# Deneigus_Sensors.net
KiCad netlist of a schematic drawn in Altium Designer
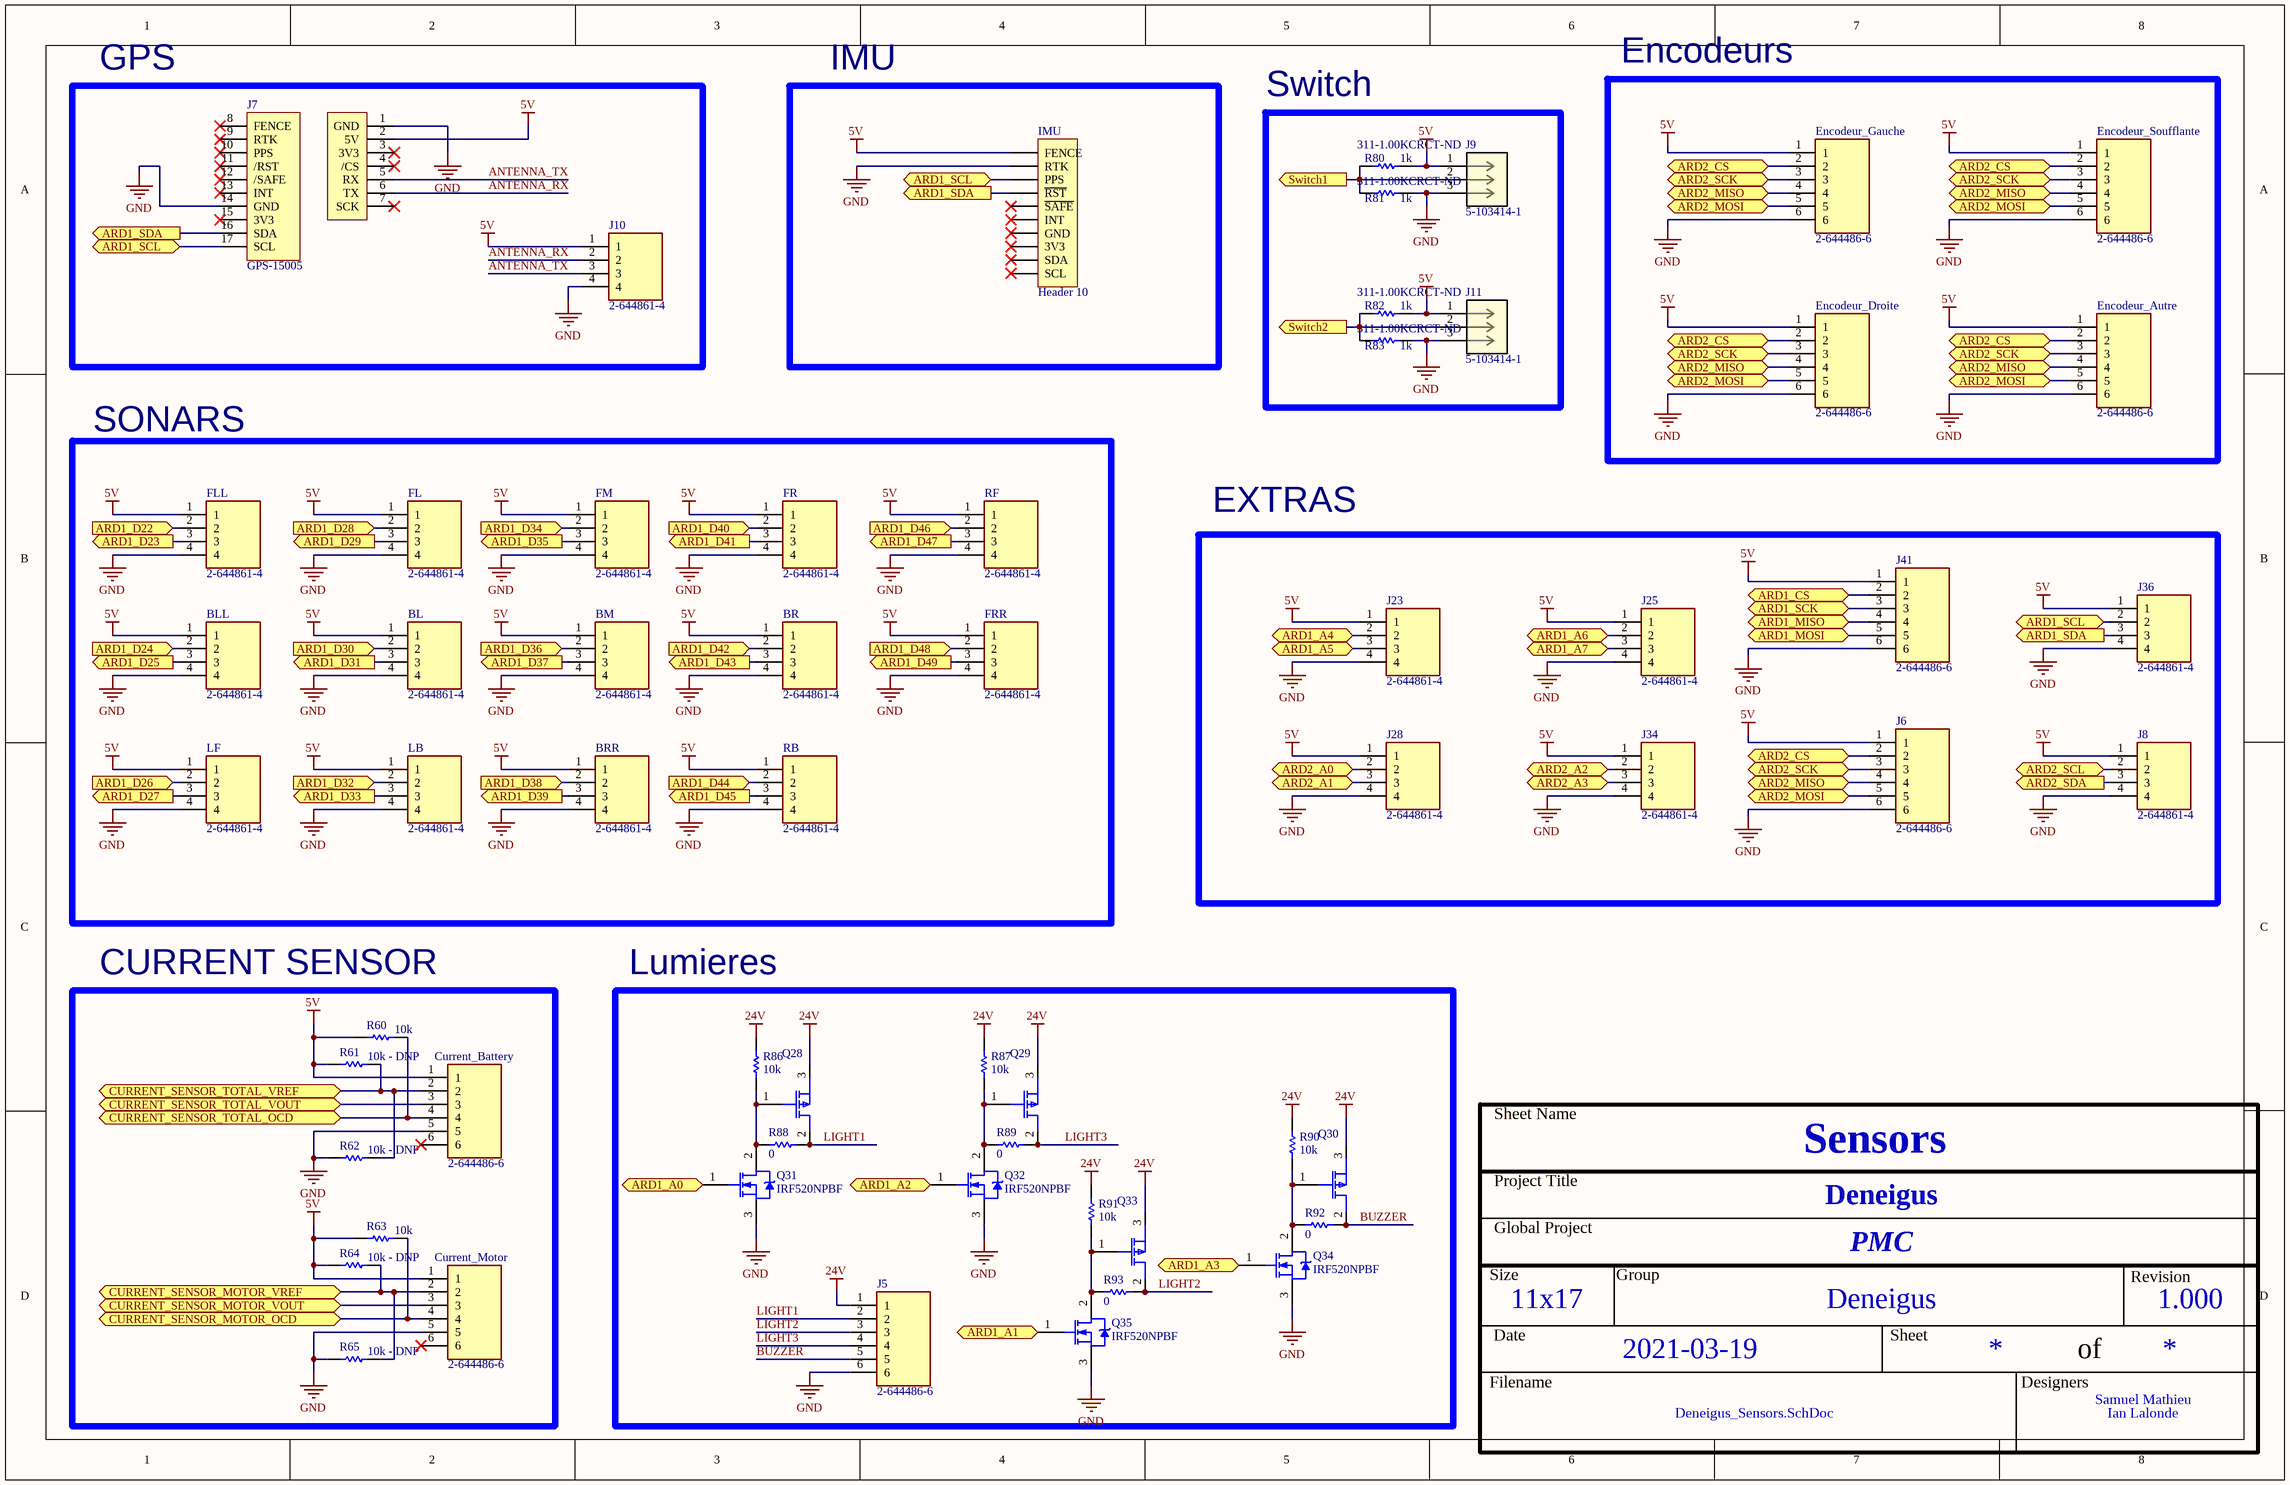
[diagram p0: Deneigus_Sensors.SchDoc]

(export (version "E")
  (design (tool "Eeschema 10.0.6"))
  (components
    (comp (ref "BL")
      (value "2-644861-4")
      (footprint "TE_2-644861-4:TE_2-644861-4")
      (description "Connector Header Through Hole 4 position 0.100 (2.54mm)")
      (fields (field (name "MF") "TE Connectivity"))
      (libsource (lib "2-644861-4") (part "2-644861-4"))
    )
    (comp (ref "BLL")
      (value "2-644861-4")
      (footprint "TE_2-644861-4:TE_2-644861-4")
      (description "Connector Header Through Hole 4 position 0.100 (2.54mm)")
      (fields (field (name "MF") "TE Connectivity"))
      (libsource (lib "2-644861-4") (part "2-644861-4"))
    )
    (comp (ref "BM")
      (value "2-644861-4")
      (footprint "TE_2-644861-4:TE_2-644861-4")
      (description "Connector Header Through Hole 4 position 0.100 (2.54mm)")
      (fields (field (name "MF") "TE Connectivity"))
      (libsource (lib "2-644861-4") (part "2-644861-4"))
    )
    (comp (ref "BR")
      (value "2-644861-4")
      (footprint "TE_2-644861-4:TE_2-644861-4")
      (description "Connector Header Through Hole 4 position 0.100 (2.54mm)")
      (fields (field (name "MF") "TE Connectivity"))
      (libsource (lib "2-644861-4") (part "2-644861-4"))
    )
    (comp (ref "BRR")
      (value "2-644861-4")
      (footprint "TE_2-644861-4:TE_2-644861-4")
      (description "Connector Header Through Hole 4 position 0.100 (2.54mm)")
      (fields (field (name "MF") "TE Connectivity"))
      (libsource (lib "2-644861-4") (part "2-644861-4"))
    )
    (comp (ref "Current_Battery")
      (value "2-644486-6")
      (footprint "TE_2-644486-6")
      (description "06P MTA100 SHRDED HDR ASSY SN")
      (fields (field (name "MF") "TE Connectivity") (field (name "DIGI-KEY_PART_NUMBER") "A30896-ND"))
      (libsource (lib "6pins_2") (part "2-644486-6"))
    )
    (comp (ref "Current_Motor")
      (value "2-644486-6")
      (footprint "TE_2-644486-6")
      (description "06P MTA100 SHRDED HDR ASSY SN")
      (fields (field (name "MF") "TE Connectivity") (field (name "DIGI-KEY_PART_NUMBER") "A30896-ND"))
      (libsource (lib "6pins_2") (part "2-644486-6"))
    )
    (comp (ref "Encodeur_Autre")
      (value "2-644486-6")
      (footprint "TE_2-644486-6")
      (description "06P MTA100 SHRDED HDR ASSY SN")
      (fields (field (name "MF") "TE Connectivity") (field (name "DIGI-KEY_PART_NUMBER") "A30896-ND"))
      (libsource (lib "6pins_2") (part "2-644486-6"))
    )
    (comp (ref "Encodeur_Droite")
      (value "2-644486-6")
      (footprint "TE_2-644486-6")
      (description "06P MTA100 SHRDED HDR ASSY SN")
      (fields (field (name "MF") "TE Connectivity") (field (name "DIGI-KEY_PART_NUMBER") "A30896-ND"))
      (libsource (lib "6pins_2") (part "2-644486-6"))
    )
    (comp (ref "Encodeur_Gauche")
      (value "2-644486-6")
      (footprint "TE_2-644486-6")
      (description "06P MTA100 SHRDED HDR ASSY SN")
      (fields (field (name "MF") "TE Connectivity") (field (name "DIGI-KEY_PART_NUMBER") "A30896-ND"))
      (libsource (lib "6pins_2") (part "2-644486-6"))
    )
    (comp (ref "Encodeur_Soufflante")
      (value "2-644486-6")
      (footprint "TE_2-644486-6")
      (description "06P MTA100 SHRDED HDR ASSY SN")
      (fields (field (name "MF") "TE Connectivity") (field (name "DIGI-KEY_PART_NUMBER") "A30896-ND"))
      (libsource (lib "6pins_2") (part "2-644486-6"))
    )
    (comp (ref "FL")
      (value "2-644861-4")
      (footprint "TE_2-644861-4:TE_2-644861-4")
      (description "Connector Header Through Hole 4 position 0.100 (2.54mm)")
      (fields (field (name "MF") "TE Connectivity"))
      (libsource (lib "2-644861-4") (part "2-644861-4"))
    )
    (comp (ref "FLL")
      (value "2-644861-4")
      (footprint "TE_2-644861-4:TE_2-644861-4")
      (description "Connector Header Through Hole 4 position 0.100 (2.54mm)")
      (fields (field (name "MF") "TE Connectivity"))
      (libsource (lib "2-644861-4") (part "2-644861-4"))
    )
    (comp (ref "FM")
      (value "2-644861-4")
      (footprint "TE_2-644861-4:TE_2-644861-4")
      (description "Connector Header Through Hole 4 position 0.100 (2.54mm)")
      (fields (field (name "MF") "TE Connectivity"))
      (libsource (lib "2-644861-4") (part "2-644861-4"))
    )
    (comp (ref "FR")
      (value "2-644861-4")
      (footprint "TE_2-644861-4:TE_2-644861-4")
      (description "Connector Header Through Hole 4 position 0.100 (2.54mm)")
      (fields (field (name "MF") "TE Connectivity"))
      (libsource (lib "2-644861-4") (part "2-644861-4"))
    )
    (comp (ref "FRR")
      (value "2-644861-4")
      (footprint "TE_2-644861-4:TE_2-644861-4")
      (description "Connector Header Through Hole 4 position 0.100 (2.54mm)")
      (fields (field (name "MF") "TE Connectivity"))
      (libsource (lib "2-644861-4") (part "2-644861-4"))
    )
    (comp (ref "IMU")
      (value "Header 10")
      (footprint "S7CAS-APP1:HDR1X10")
      (description "Header, 10-Pin")
      (fields (field (name "PUBLISHER") "Altium Limited"))
      (libsource (lib "Miscellaneous Connectors") (part "Header 10"))
    )
    (comp (ref "J5")
      (value "2-644486-6")
      (footprint "TE_2-644486-6")
      (description "06P MTA100 SHRDED HDR ASSY SN")
      (fields (field (name "MF") "TE Connectivity") (field (name "DIGI-KEY_PART_NUMBER") "A30896-ND"))
      (libsource (lib "6pins_2") (part "2-644486-6"))
    )
    (comp (ref "J6")
      (value "2-644486-6")
      (footprint "TE_2-644486-6")
      (description "06P MTA100 SHRDED HDR ASSY SN")
      (fields (field (name "MF") "TE Connectivity") (field (name "DIGI-KEY_PART_NUMBER") "A30896-ND"))
      (libsource (lib "6pins_2") (part "2-644486-6"))
    )
    (comp (ref "J7")
      (value "GPS-15005")
      (footprint "GPS_PFB")
      (libsource (lib "S7CAS-APP1") (part "GPS_PFB"))
    )
    (comp (ref "J8")
      (value "2-644861-4")
      (footprint "TE_2-644861-4:TE_2-644861-4")
      (description "Connector Header Through Hole 4 position 0.100 (2.54mm)")
      (fields (field (name "MF") "TE Connectivity"))
      (libsource (lib "2-644861-4") (part "2-644861-4"))
    )
    (comp (ref "J9")
      (value "5-103414-1")
      (footprint "2021-04-13_19-21-58:CONN_5-103414-1_TYCO")
      (description "No Description Available")
      (fields (field (name "COPYRIGHT") "Copyright (C) 2016 Accelerated Designs. All rights reserved"))
      (libsource (lib "3pins") (part "5-103414-1"))
    )
    (comp (ref "J10")
      (value "2-644861-4")
      (footprint "TE_2-644861-4:TE_2-644861-4")
      (description "Connector Header Through Hole 4 position 0.100 (2.54mm)")
      (fields (field (name "MF") "TE Connectivity"))
      (libsource (lib "2-644861-4") (part "2-644861-4"))
    )
    (comp (ref "J11")
      (value "5-103414-1")
      (footprint "2021-04-13_19-21-58:CONN_5-103414-1_TYCO")
      (description "No Description Available")
      (fields (field (name "COPYRIGHT") "Copyright (C) 2016 Accelerated Designs. All rights reserved"))
      (libsource (lib "3pins") (part "5-103414-1"))
    )
    (comp (ref "J23")
      (value "2-644861-4")
      (footprint "TE_2-644861-4:TE_2-644861-4")
      (description "Connector Header Through Hole 4 position 0.100 (2.54mm)")
      (fields (field (name "MF") "TE Connectivity"))
      (libsource (lib "2-644861-4") (part "2-644861-4"))
    )
    (comp (ref "J25")
      (value "2-644861-4")
      (footprint "TE_2-644861-4:TE_2-644861-4")
      (description "Connector Header Through Hole 4 position 0.100 (2.54mm)")
      (fields (field (name "MF") "TE Connectivity"))
      (libsource (lib "2-644861-4") (part "2-644861-4"))
    )
    (comp (ref "J28")
      (value "2-644861-4")
      (footprint "TE_2-644861-4:TE_2-644861-4")
      (description "Connector Header Through Hole 4 position 0.100 (2.54mm)")
      (fields (field (name "MF") "TE Connectivity"))
      (libsource (lib "2-644861-4") (part "2-644861-4"))
    )
    (comp (ref "J34")
      (value "2-644861-4")
      (footprint "TE_2-644861-4:TE_2-644861-4")
      (description "Connector Header Through Hole 4 position 0.100 (2.54mm)")
      (fields (field (name "MF") "TE Connectivity"))
      (libsource (lib "2-644861-4") (part "2-644861-4"))
    )
    (comp (ref "J36")
      (value "2-644861-4")
      (footprint "TE_2-644861-4:TE_2-644861-4")
      (description "Connector Header Through Hole 4 position 0.100 (2.54mm)")
      (fields (field (name "MF") "TE Connectivity"))
      (libsource (lib "2-644861-4") (part "2-644861-4"))
    )
    (comp (ref "J41")
      (value "2-644486-6")
      (footprint "TE_2-644486-6")
      (description "06P MTA100 SHRDED HDR ASSY SN")
      (fields (field (name "MF") "TE Connectivity") (field (name "DIGI-KEY_PART_NUMBER") "A30896-ND"))
      (libsource (lib "6pins_2") (part "2-644486-6"))
    )
    (comp (ref "LB")
      (value "2-644861-4")
      (footprint "TE_2-644861-4:TE_2-644861-4")
      (description "Connector Header Through Hole 4 position 0.100 (2.54mm)")
      (fields (field (name "MF") "TE Connectivity"))
      (libsource (lib "2-644861-4") (part "2-644861-4"))
    )
    (comp (ref "LF")
      (value "2-644861-4")
      (footprint "TE_2-644861-4:TE_2-644861-4")
      (description "Connector Header Through Hole 4 position 0.100 (2.54mm)")
      (fields (field (name "MF") "TE Connectivity"))
      (libsource (lib "2-644861-4") (part "2-644861-4"))
    )
    (comp (ref "Q28")
      (value "MOSFET P-CH 55V 12A TO220AB")
      (footprint "IRF9Z24NPBF")
      (libsource (lib "S7CAS-APP1") (part "IRF9Z24NPBF"))
    )
    (comp (ref "Q29")
      (value "MOSFET P-CH 55V 12A TO220AB")
      (footprint "IRF9Z24NPBF")
      (libsource (lib "S7CAS-APP1") (part "IRF9Z24NPBF"))
    )
    (comp (ref "Q30")
      (value "MOSFET P-CH 55V 12A TO220AB")
      (footprint "IRF9Z24NPBF")
      (libsource (lib "S7CAS-APP1") (part "IRF9Z24NPBF"))
    )
    (comp (ref "Q31")
      (value "IRF520NPBF")
      (footprint "INTR-TO-220AB-3")
      (description "HEXFET(R) Power MOSFET, 100 V, 9.7 A, 0.2 Ohm, -55 to 175 degC, 3-Pin FM (TO-220AB), RoHS, Tube")
      (fields (field (name "POWER") "48W") (field (name "MANUFACTURER") "International Rectifier"))
      (libsource (lib "Université de Sherbrooke") (part "NEMOS-GDS-3_B"))
    )
    (comp (ref "Q32")
      (value "IRF520NPBF")
      (footprint "INTR-TO-220AB-3")
      (description "HEXFET(R) Power MOSFET, 100 V, 9.7 A, 0.2 Ohm, -55 to 175 degC, 3-Pin FM (TO-220AB), RoHS, Tube")
      (fields (field (name "POWER") "48W") (field (name "MANUFACTURER") "International Rectifier"))
      (libsource (lib "Université de Sherbrooke") (part "NEMOS-GDS-3_B"))
    )
    (comp (ref "Q33")
      (value "MOSFET P-CH 55V 12A TO220AB")
      (footprint "IRF9Z24NPBF")
      (libsource (lib "S7CAS-APP1") (part "IRF9Z24NPBF"))
    )
    (comp (ref "Q34")
      (value "IRF520NPBF")
      (footprint "INTR-TO-220AB-3")
      (description "HEXFET(R) Power MOSFET, 100 V, 9.7 A, 0.2 Ohm, -55 to 175 degC, 3-Pin FM (TO-220AB), RoHS, Tube")
      (fields (field (name "POWER") "48W") (field (name "MANUFACTURER") "International Rectifier"))
      (libsource (lib "Université de Sherbrooke") (part "NEMOS-GDS-3_B"))
    )
    (comp (ref "Q35")
      (value "IRF520NPBF")
      (footprint "INTR-TO-220AB-3")
      (description "HEXFET(R) Power MOSFET, 100 V, 9.7 A, 0.2 Ohm, -55 to 175 degC, 3-Pin FM (TO-220AB), RoHS, Tube")
      (fields (field (name "POWER") "48W") (field (name "MANUFACTURER") "International Rectifier"))
      (libsource (lib "Université de Sherbrooke") (part "NEMOS-GDS-3_B"))
    )
    (comp (ref "R60")
      (value "10k")
      (footprint "RES_0805")
      (description "Resistor")
      (fields (field (name "Comment") "Res1") (field (name "PUBLISHER") "Altium Limited"))
      (libsource (lib "Miscellaneous Devices") (part "Res1"))
    )
    (comp (ref "R61")
      (value "10k - DNP")
      (footprint "RES_0805")
      (description "Resistor")
      (fields (field (name "Comment") "Res1") (field (name "PUBLISHER") "Altium Limited"))
      (libsource (lib "Miscellaneous Devices") (part "Res1"))
    )
    (comp (ref "R62")
      (value "10k - DNP")
      (footprint "RES_0805")
      (description "Resistor")
      (fields (field (name "Comment") "Res1") (field (name "PUBLISHER") "Altium Limited"))
      (libsource (lib "Miscellaneous Devices") (part "Res1"))
    )
    (comp (ref "R63")
      (value "10k")
      (footprint "RES_0805")
      (description "Resistor")
      (fields (field (name "Comment") "Res1") (field (name "PUBLISHER") "Altium Limited"))
      (libsource (lib "Miscellaneous Devices") (part "Res1"))
    )
    (comp (ref "R64")
      (value "10k - DNP")
      (footprint "RES_0805")
      (description "Resistor")
      (fields (field (name "Comment") "Res1") (field (name "PUBLISHER") "Altium Limited"))
      (libsource (lib "Miscellaneous Devices") (part "Res1"))
    )
    (comp (ref "R65")
      (value "10k - DNP")
      (footprint "RES_0805")
      (description "Resistor")
      (fields (field (name "Comment") "Res1") (field (name "PUBLISHER") "Altium Limited"))
      (libsource (lib "Miscellaneous Devices") (part "Res1"))
    )
    (comp (ref "R80")
      (value "1k")
      (footprint "RES_0805")
      (description "RES - 0805")
      (fields
        (field (name "SUPPLIER PART NUMBER 1") "311-1.00KCRCT-ND")
        (field (name "CREATEDBY") "Jonathan Bouchard")
      )
      (libsource (lib "S7CAS_LIB2021") (part "RES - 0805"))
    )
    (comp (ref "R81")
      (value "1k")
      (footprint "RES_0805")
      (description "RES - 0805")
      (fields
        (field (name "SUPPLIER PART NUMBER 1") "311-1.00KCRCT-ND")
        (field (name "CREATEDBY") "Jonathan Bouchard")
      )
      (libsource (lib "S7CAS_LIB2021") (part "RES - 0805"))
    )
    (comp (ref "R82")
      (value "1k")
      (footprint "RES_0805")
      (description "RES - 0805")
      (fields
        (field (name "SUPPLIER PART NUMBER 1") "311-1.00KCRCT-ND")
        (field (name "CREATEDBY") "Jonathan Bouchard")
      )
      (libsource (lib "S7CAS_LIB2021") (part "RES - 0805"))
    )
    (comp (ref "R83")
      (value "1k")
      (footprint "RES_0805")
      (description "RES - 0805")
      (fields
        (field (name "SUPPLIER PART NUMBER 1") "311-1.00KCRCT-ND")
        (field (name "CREATEDBY") "Jonathan Bouchard")
      )
      (libsource (lib "S7CAS_LIB2021") (part "RES - 0805"))
    )
    (comp (ref "R86")
      (value "10k")
      (footprint "RES_0805")
      (description "Resistor")
      (fields (field (name "Comment") "Res1") (field (name "PUBLISHER") "Altium Limited"))
      (libsource (lib "Miscellaneous Devices") (part "Res1"))
    )
    (comp (ref "R87")
      (value "10k")
      (footprint "RES_0805")
      (description "Resistor")
      (fields (field (name "Comment") "Res1") (field (name "PUBLISHER") "Altium Limited"))
      (libsource (lib "Miscellaneous Devices") (part "Res1"))
    )
    (comp (ref "R88")
      (value "0")
      (footprint "RES_0805")
      (description "Resistor")
      (fields (field (name "Comment") "Res1") (field (name "PUBLISHER") "Altium Limited"))
      (libsource (lib "Miscellaneous Devices") (part "Res1"))
    )
    (comp (ref "R89")
      (value "0")
      (footprint "RES_0805")
      (description "Resistor")
      (fields (field (name "Comment") "Res1") (field (name "PUBLISHER") "Altium Limited"))
      (libsource (lib "Miscellaneous Devices") (part "Res1"))
    )
    (comp (ref "R90")
      (value "10k")
      (footprint "RES_0805")
      (description "Resistor")
      (fields (field (name "Comment") "Res1") (field (name "PUBLISHER") "Altium Limited"))
      (libsource (lib "Miscellaneous Devices") (part "Res1"))
    )
    (comp (ref "R91")
      (value "10k")
      (footprint "RES_0805")
      (description "Resistor")
      (fields (field (name "Comment") "Res1") (field (name "PUBLISHER") "Altium Limited"))
      (libsource (lib "Miscellaneous Devices") (part "Res1"))
    )
    (comp (ref "R92")
      (value "0")
      (footprint "RES_0805")
      (description "Resistor")
      (fields (field (name "Comment") "Res1") (field (name "PUBLISHER") "Altium Limited"))
      (libsource (lib "Miscellaneous Devices") (part "Res1"))
    )
    (comp (ref "R93")
      (value "0")
      (footprint "RES_0805")
      (description "Resistor")
      (fields (field (name "Comment") "Res1") (field (name "PUBLISHER") "Altium Limited"))
      (libsource (lib "Miscellaneous Devices") (part "Res1"))
    )
    (comp (ref "RB")
      (value "2-644861-4")
      (footprint "TE_2-644861-4:TE_2-644861-4")
      (description "Connector Header Through Hole 4 position 0.100 (2.54mm)")
      (fields (field (name "MF") "TE Connectivity"))
      (libsource (lib "2-644861-4") (part "2-644861-4"))
    )
    (comp (ref "RF")
      (value "2-644861-4")
      (footprint "TE_2-644861-4:TE_2-644861-4")
      (description "Connector Header Through Hole 4 position 0.100 (2.54mm)")
      (fields (field (name "MF") "TE Connectivity"))
      (libsource (lib "2-644861-4") (part "2-644861-4"))
    )
  )
  (nets
    (net (code "1") (name "/ANTENNA_RX") (class "Default")
      (node (ref "J10") (pin "2") (pinfunction "2_2") (pintype "passive"))
      (node (ref "J7") (pin "6") (pinfunction "TX_6") (pintype "passive"))
    )
    (net (code "2") (name "/ANTENNA_TX") (class "Default")
      (node (ref "J10") (pin "3") (pinfunction "3_3") (pintype "passive"))
      (node (ref "J7") (pin "5") (pinfunction "RX_5") (pintype "passive"))
    )
    (net (code "3") (name "/ARD1_A0") (class "Default")
      (node (ref "Q31") (pin "1") (pinfunction "G_1") (pintype "passive"))
    )
    (net (code "4") (name "/ARD1_A1") (class "Default")
      (node (ref "Q35") (pin "1") (pinfunction "G_1") (pintype "passive"))
    )
    (net (code "5") (name "/ARD1_A2") (class "Default")
      (node (ref "Q32") (pin "1") (pinfunction "G_1") (pintype "passive"))
    )
    (net (code "6") (name "/ARD1_A3") (class "Default")
      (node (ref "Q34") (pin "1") (pinfunction "G_1") (pintype "passive"))
    )
    (net (code "7") (name "/ARD1_A4") (class "Default")
      (node (ref "J23") (pin "2") (pinfunction "2_2") (pintype "passive"))
    )
    (net (code "8") (name "/ARD1_A5") (class "Default")
      (node (ref "J23") (pin "3") (pinfunction "3_3") (pintype "passive"))
    )
    (net (code "9") (name "/ARD1_A6") (class "Default")
      (node (ref "J25") (pin "2") (pinfunction "2_2") (pintype "passive"))
    )
    (net (code "10") (name "/ARD1_A7") (class "Default")
      (node (ref "J25") (pin "3") (pinfunction "3_3") (pintype "passive"))
    )
    (net (code "11") (name "/ARD1_CS") (class "Default")
      (node (ref "J41") (pin "2") (pinfunction "2_2") (pintype "passive"))
    )
    (net (code "12") (name "/ARD1_D22") (class "Default")
      (node (ref "FLL") (pin "2") (pinfunction "2_2") (pintype "passive"))
    )
    (net (code "13") (name "/ARD1_D23") (class "Default")
      (node (ref "FLL") (pin "3") (pinfunction "3_3") (pintype "passive"))
    )
    (net (code "14") (name "/ARD1_D24") (class "Default")
      (node (ref "BLL") (pin "2") (pinfunction "2_2") (pintype "passive"))
    )
    (net (code "15") (name "/ARD1_D25") (class "Default")
      (node (ref "BLL") (pin "3") (pinfunction "3_3") (pintype "passive"))
    )
    (net (code "16") (name "/ARD1_D26") (class "Default")
      (node (ref "LF") (pin "2") (pinfunction "2_2") (pintype "passive"))
    )
    (net (code "17") (name "/ARD1_D27") (class "Default")
      (node (ref "LF") (pin "3") (pinfunction "3_3") (pintype "passive"))
    )
    (net (code "18") (name "/ARD1_D28") (class "Default")
      (node (ref "FL") (pin "2") (pinfunction "2_2") (pintype "passive"))
    )
    (net (code "19") (name "/ARD1_D29") (class "Default")
      (node (ref "FL") (pin "3") (pinfunction "3_3") (pintype "passive"))
    )
    (net (code "20") (name "/ARD1_D30") (class "Default")
      (node (ref "BL") (pin "2") (pinfunction "2_2") (pintype "passive"))
    )
    (net (code "21") (name "/ARD1_D31") (class "Default")
      (node (ref "BL") (pin "3") (pinfunction "3_3") (pintype "passive"))
    )
    (net (code "22") (name "/ARD1_D32") (class "Default")
      (node (ref "LB") (pin "2") (pinfunction "2_2") (pintype "passive"))
    )
    (net (code "23") (name "/ARD1_D33") (class "Default")
      (node (ref "LB") (pin "3") (pinfunction "3_3") (pintype "passive"))
    )
    (net (code "24") (name "/ARD1_D34") (class "Default")
      (node (ref "FM") (pin "2") (pinfunction "2_2") (pintype "passive"))
    )
    (net (code "25") (name "/ARD1_D35") (class "Default")
      (node (ref "FM") (pin "3") (pinfunction "3_3") (pintype "passive"))
    )
    (net (code "26") (name "/ARD1_D36") (class "Default")
      (node (ref "BM") (pin "2") (pinfunction "2_2") (pintype "passive"))
    )
    (net (code "27") (name "/ARD1_D37") (class "Default")
      (node (ref "BM") (pin "3") (pinfunction "3_3") (pintype "passive"))
    )
    (net (code "28") (name "/ARD1_D38") (class "Default")
      (node (ref "BRR") (pin "2") (pinfunction "2_2") (pintype "passive"))
    )
    (net (code "29") (name "/ARD1_D39") (class "Default")
      (node (ref "BRR") (pin "3") (pinfunction "3_3") (pintype "passive"))
    )
    (net (code "30") (name "/ARD1_D40") (class "Default")
      (node (ref "FR") (pin "2") (pinfunction "2_2") (pintype "passive"))
    )
    (net (code "31") (name "/ARD1_D41") (class "Default")
      (node (ref "FR") (pin "3") (pinfunction "3_3") (pintype "passive"))
    )
    (net (code "32") (name "/ARD1_D42") (class "Default")
      (node (ref "BR") (pin "2") (pinfunction "2_2") (pintype "passive"))
    )
    (net (code "33") (name "/ARD1_D43") (class "Default")
      (node (ref "BR") (pin "3") (pinfunction "3_3") (pintype "passive"))
    )
    (net (code "34") (name "/ARD1_D44") (class "Default")
      (node (ref "RB") (pin "2") (pinfunction "2_2") (pintype "passive"))
    )
    (net (code "35") (name "/ARD1_D45") (class "Default")
      (node (ref "RB") (pin "3") (pinfunction "3_3") (pintype "passive"))
    )
    (net (code "36") (name "/ARD1_D46") (class "Default")
      (node (ref "RF") (pin "2") (pinfunction "2_2") (pintype "passive"))
    )
    (net (code "37") (name "/ARD1_D47") (class "Default")
      (node (ref "RF") (pin "3") (pinfunction "3_3") (pintype "passive"))
    )
    (net (code "38") (name "/ARD1_D48") (class "Default")
      (node (ref "FRR") (pin "2") (pinfunction "2_2") (pintype "passive"))
    )
    (net (code "39") (name "/ARD1_D49") (class "Default")
      (node (ref "FRR") (pin "3") (pinfunction "3_3") (pintype "passive"))
    )
    (net (code "40") (name "/ARD1_MISO") (class "Default")
      (node (ref "J41") (pin "4") (pinfunction "4_4") (pintype "passive"))
    )
    (net (code "41") (name "/ARD1_MOSI") (class "Default")
      (node (ref "J41") (pin "5") (pinfunction "5_5") (pintype "passive"))
    )
    (net (code "42") (name "/ARD1_SCK") (class "Default")
      (node (ref "J41") (pin "3") (pinfunction "3_3") (pintype "passive"))
    )
    (net (code "43") (name "/ARD1_SCL") (class "Default")
      (node (ref "IMU") (pin "3") (pinfunction "PPS_3") (pintype "passive"))
      (node (ref "J36") (pin "2") (pinfunction "2_2") (pintype "passive"))
      (node (ref "J7") (pin "17") (pinfunction "SCL_17") (pintype "passive"))
    )
    (net (code "44") (name "/ARD1_SDA") (class "Default")
      (node (ref "IMU") (pin "4") (pinfunction "RST_4") (pintype "passive"))
      (node (ref "J36") (pin "3") (pinfunction "3_3") (pintype "passive"))
      (node (ref "J7") (pin "16") (pinfunction "SDA_16") (pintype "passive"))
    )
    (net (code "45") (name "/ARD2_A0") (class "Default")
      (node (ref "J28") (pin "2") (pinfunction "2_2") (pintype "passive"))
    )
    (net (code "46") (name "/ARD2_A1") (class "Default")
      (node (ref "J28") (pin "3") (pinfunction "3_3") (pintype "passive"))
    )
    (net (code "47") (name "/ARD2_A2") (class "Default")
      (node (ref "J34") (pin "2") (pinfunction "2_2") (pintype "passive"))
    )
    (net (code "48") (name "/ARD2_A3") (class "Default")
      (node (ref "J34") (pin "3") (pinfunction "3_3") (pintype "passive"))
    )
    (net (code "49") (name "/ARD2_CS") (class "Default")
      (node (ref "Encodeur_Autre") (pin "2") (pinfunction "2_2") (pintype "passive"))
      (node (ref "Encodeur_Droite") (pin "2") (pinfunction "2_2") (pintype "passive"))
      (node (ref "Encodeur_Gauche") (pin "2") (pinfunction "2_2") (pintype "passive"))
      (node (ref "Encodeur_Soufflante") (pin "2") (pinfunction "2_2") (pintype "passive"))
      (node (ref "J6") (pin "2") (pinfunction "2_2") (pintype "passive"))
    )
    (net (code "50") (name "/ARD2_MISO") (class "Default")
      (node (ref "Encodeur_Autre") (pin "4") (pinfunction "4_4") (pintype "passive"))
      (node (ref "Encodeur_Droite") (pin "4") (pinfunction "4_4") (pintype "passive"))
      (node (ref "Encodeur_Gauche") (pin "4") (pinfunction "4_4") (pintype "passive"))
      (node (ref "Encodeur_Soufflante") (pin "4") (pinfunction "4_4") (pintype "passive"))
      (node (ref "J6") (pin "4") (pinfunction "4_4") (pintype "passive"))
    )
    (net (code "51") (name "/ARD2_MOSI") (class "Default")
      (node (ref "Encodeur_Autre") (pin "5") (pinfunction "5_5") (pintype "passive"))
      (node (ref "Encodeur_Droite") (pin "5") (pinfunction "5_5") (pintype "passive"))
      (node (ref "Encodeur_Gauche") (pin "5") (pinfunction "5_5") (pintype "passive"))
      (node (ref "Encodeur_Soufflante") (pin "5") (pinfunction "5_5") (pintype "passive"))
      (node (ref "J6") (pin "5") (pinfunction "5_5") (pintype "passive"))
    )
    (net (code "52") (name "/ARD2_SCK") (class "Default")
      (node (ref "Encodeur_Autre") (pin "3") (pinfunction "3_3") (pintype "passive"))
      (node (ref "Encodeur_Droite") (pin "3") (pinfunction "3_3") (pintype "passive"))
      (node (ref "Encodeur_Gauche") (pin "3") (pinfunction "3_3") (pintype "passive"))
      (node (ref "Encodeur_Soufflante") (pin "3") (pinfunction "3_3") (pintype "passive"))
      (node (ref "J6") (pin "3") (pinfunction "3_3") (pintype "passive"))
    )
    (net (code "53") (name "/ARD2_SCL") (class "Default")
      (node (ref "J8") (pin "2") (pinfunction "2_2") (pintype "passive"))
    )
    (net (code "54") (name "/ARD2_SDA") (class "Default")
      (node (ref "J8") (pin "3") (pinfunction "3_3") (pintype "passive"))
    )
    (net (code "55") (name "/BUZZER") (class "Default")
      (node (ref "J5") (pin "5") (pinfunction "5_5") (pintype "passive"))
      (node (ref "Q30") (pin "2") (pinfunction "Drain_2") (pintype "passive"))
      (node (ref "R92") (pin "2") (pinfunction "2_2") (pintype "passive"))
    )
    (net (code "56") (name "/CURRENT_SENSOR_MOTOR_OCD") (class "Default")
      (node (ref "Current_Motor") (pin "4") (pinfunction "4_4") (pintype "passive"))
      (node (ref "R63") (pin "1") (pinfunction "1_1") (pintype "passive"))
    )
    (net (code "57") (name "/CURRENT_SENSOR_MOTOR_VOUT") (class "Default")
      (node (ref "Current_Motor") (pin "3") (pinfunction "3_3") (pintype "passive"))
    )
    (net (code "58") (name "/CURRENT_SENSOR_MOTOR_VREF") (class "Default")
      (node (ref "Current_Motor") (pin "2") (pinfunction "2_2") (pintype "passive"))
      (node (ref "R64") (pin "1") (pinfunction "1_1") (pintype "passive"))
      (node (ref "R65") (pin "1") (pinfunction "1_1") (pintype "passive"))
    )
    (net (code "59") (name "/CURRENT_SENSOR_TOTAL_OCD") (class "Default")
      (node (ref "Current_Battery") (pin "4") (pinfunction "4_4") (pintype "passive"))
      (node (ref "R60") (pin "1") (pinfunction "1_1") (pintype "passive"))
    )
    (net (code "60") (name "/CURRENT_SENSOR_TOTAL_VOUT") (class "Default")
      (node (ref "Current_Battery") (pin "3") (pinfunction "3_3") (pintype "passive"))
    )
    (net (code "61") (name "/CURRENT_SENSOR_TOTAL_VREF") (class "Default")
      (node (ref "Current_Battery") (pin "2") (pinfunction "2_2") (pintype "passive"))
      (node (ref "R61") (pin "1") (pinfunction "1_1") (pintype "passive"))
      (node (ref "R62") (pin "1") (pinfunction "1_1") (pintype "passive"))
    )
    (net (code "62") (name "/LIGHT1") (class "Default")
      (node (ref "J5") (pin "2") (pinfunction "2_2") (pintype "passive"))
      (node (ref "Q28") (pin "2") (pinfunction "Drain_2") (pintype "passive"))
      (node (ref "R88") (pin "2") (pinfunction "2_2") (pintype "passive"))
    )
    (net (code "63") (name "/LIGHT2") (class "Default")
      (node (ref "J5") (pin "3") (pinfunction "3_3") (pintype "passive"))
      (node (ref "Q33") (pin "2") (pinfunction "Drain_2") (pintype "passive"))
      (node (ref "R93") (pin "2") (pinfunction "2_2") (pintype "passive"))
    )
    (net (code "64") (name "/LIGHT3") (class "Default")
      (node (ref "J5") (pin "4") (pinfunction "4_4") (pintype "passive"))
      (node (ref "Q29") (pin "2") (pinfunction "Drain_2") (pintype "passive"))
      (node (ref "R89") (pin "2") (pinfunction "2_2") (pintype "passive"))
    )
    (net (code "65") (name "/Switch1") (class "Default")
      (node (ref "J9") (pin "2") (pinfunction "2_2") (pintype "passive"))
      (node (ref "R80") (pin "1") (pinfunction "1_1") (pintype "passive"))
      (node (ref "R81") (pin "2") (pinfunction "2_2") (pintype "passive"))
    )
    (net (code "66") (name "/Switch2") (class "Default")
      (node (ref "J11") (pin "2") (pinfunction "2_2") (pintype "passive"))
      (node (ref "R82") (pin "1") (pinfunction "1_1") (pintype "passive"))
      (node (ref "R83") (pin "2") (pinfunction "2_2") (pintype "passive"))
    )
    (net (code "67") (name "5V") (class "Default")
      (node (ref "BL") (pin "1") (pinfunction "1_1") (pintype "passive"))
      (node (ref "BLL") (pin "1") (pinfunction "1_1") (pintype "passive"))
      (node (ref "BM") (pin "1") (pinfunction "1_1") (pintype "passive"))
      (node (ref "BR") (pin "1") (pinfunction "1_1") (pintype "passive"))
      (node (ref "BRR") (pin "1") (pinfunction "1_1") (pintype "passive"))
      (node (ref "Current_Battery") (pin "1") (pinfunction "1_1") (pintype "passive"))
      (node (ref "Current_Motor") (pin "1") (pinfunction "1_1") (pintype "passive"))
      (node (ref "Encodeur_Autre") (pin "1") (pinfunction "1_1") (pintype "passive"))
      (node (ref "Encodeur_Droite") (pin "1") (pinfunction "1_1") (pintype "passive"))
      (node (ref "Encodeur_Gauche") (pin "1") (pinfunction "1_1") (pintype "passive"))
      (node (ref "Encodeur_Soufflante") (pin "1") (pinfunction "1_1") (pintype "passive"))
      (node (ref "FL") (pin "1") (pinfunction "1_1") (pintype "passive"))
      (node (ref "FLL") (pin "1") (pinfunction "1_1") (pintype "passive"))
      (node (ref "FM") (pin "1") (pinfunction "1_1") (pintype "passive"))
      (node (ref "FR") (pin "1") (pinfunction "1_1") (pintype "passive"))
      (node (ref "FRR") (pin "1") (pinfunction "1_1") (pintype "passive"))
      (node (ref "IMU") (pin "1") (pinfunction "FENCE_1") (pintype "passive"))
      (node (ref "J10") (pin "1") (pinfunction "1_1") (pintype "passive"))
      (node (ref "J11") (pin "1") (pinfunction "1_1") (pintype "passive"))
      (node (ref "J23") (pin "1") (pinfunction "1_1") (pintype "passive"))
      (node (ref "J25") (pin "1") (pinfunction "1_1") (pintype "passive"))
      (node (ref "J28") (pin "1") (pinfunction "1_1") (pintype "passive"))
      (node (ref "J34") (pin "1") (pinfunction "1_1") (pintype "passive"))
      (node (ref "J36") (pin "1") (pinfunction "1_1") (pintype "passive"))
      (node (ref "J41") (pin "1") (pinfunction "1_1") (pintype "passive"))
      (node (ref "J6") (pin "1") (pinfunction "1_1") (pintype "passive"))
      (node (ref "J7") (pin "2") (pinfunction "5V_2") (pintype "passive"))
      (node (ref "J8") (pin "1") (pinfunction "1_1") (pintype "passive"))
      (node (ref "J9") (pin "1") (pinfunction "1_1") (pintype "passive"))
      (node (ref "LB") (pin "1") (pinfunction "1_1") (pintype "passive"))
      (node (ref "LF") (pin "1") (pinfunction "1_1") (pintype "passive"))
      (node (ref "R60") (pin "2") (pinfunction "2_2") (pintype "passive"))
      (node (ref "R61") (pin "2") (pinfunction "2_2") (pintype "passive"))
      (node (ref "R63") (pin "2") (pinfunction "2_2") (pintype "passive"))
      (node (ref "R64") (pin "2") (pinfunction "2_2") (pintype "passive"))
      (node (ref "R80") (pin "2") (pinfunction "2_2") (pintype "passive"))
      (node (ref "R82") (pin "2") (pinfunction "2_2") (pintype "passive"))
      (node (ref "RB") (pin "1") (pinfunction "1_1") (pintype "passive"))
      (node (ref "RF") (pin "1") (pinfunction "1_1") (pintype "passive"))
    )
    (net (code "68") (name "24V") (class "Default")
      (node (ref "J5") (pin "1") (pinfunction "1_1") (pintype "passive"))
      (node (ref "Q28") (pin "3") (pinfunction "Source_3") (pintype "passive"))
      (node (ref "Q29") (pin "3") (pinfunction "Source_3") (pintype "passive"))
      (node (ref "Q30") (pin "3") (pinfunction "Source_3") (pintype "passive"))
      (node (ref "Q33") (pin "3") (pinfunction "Source_3") (pintype "passive"))
      (node (ref "R86") (pin "1") (pinfunction "1_1") (pintype "passive"))
      (node (ref "R87") (pin "1") (pinfunction "1_1") (pintype "passive"))
      (node (ref "R90") (pin "1") (pinfunction "1_1") (pintype "passive"))
      (node (ref "R91") (pin "1") (pinfunction "1_1") (pintype "passive"))
    )
    (net (code "69") (name "GND") (class "Default")
      (node (ref "BL") (pin "4") (pinfunction "4_4") (pintype "passive"))
      (node (ref "BLL") (pin "4") (pinfunction "4_4") (pintype "passive"))
      (node (ref "BM") (pin "4") (pinfunction "4_4") (pintype "passive"))
      (node (ref "BR") (pin "4") (pinfunction "4_4") (pintype "passive"))
      (node (ref "BRR") (pin "4") (pinfunction "4_4") (pintype "passive"))
      (node (ref "Current_Battery") (pin "5") (pinfunction "5_5") (pintype "passive"))
      (node (ref "Current_Motor") (pin "5") (pinfunction "5_5") (pintype "passive"))
      (node (ref "Encodeur_Autre") (pin "6") (pinfunction "6_6") (pintype "passive"))
      (node (ref "Encodeur_Droite") (pin "6") (pinfunction "6_6") (pintype "passive"))
      (node (ref "Encodeur_Gauche") (pin "6") (pinfunction "6_6") (pintype "passive"))
      (node (ref "Encodeur_Soufflante") (pin "6") (pinfunction "6_6") (pintype "passive"))
      (node (ref "FL") (pin "4") (pinfunction "4_4") (pintype "passive"))
      (node (ref "FLL") (pin "4") (pinfunction "4_4") (pintype "passive"))
      (node (ref "FM") (pin "4") (pinfunction "4_4") (pintype "passive"))
      (node (ref "FR") (pin "4") (pinfunction "4_4") (pintype "passive"))
      (node (ref "FRR") (pin "4") (pinfunction "4_4") (pintype "passive"))
      (node (ref "IMU") (pin "2") (pinfunction "RTK_2") (pintype "passive"))
      (node (ref "J10") (pin "4") (pinfunction "4_4") (pintype "passive"))
      (node (ref "J11") (pin "3") (pinfunction "3_3") (pintype "passive"))
      (node (ref "J23") (pin "4") (pinfunction "4_4") (pintype "passive"))
      (node (ref "J25") (pin "4") (pinfunction "4_4") (pintype "passive"))
      (node (ref "J28") (pin "4") (pinfunction "4_4") (pintype "passive"))
      (node (ref "J34") (pin "4") (pinfunction "4_4") (pintype "passive"))
      (node (ref "J36") (pin "4") (pinfunction "4_4") (pintype "passive"))
      (node (ref "J41") (pin "6") (pinfunction "6_6") (pintype "passive"))
      (node (ref "J5") (pin "6") (pinfunction "6_6") (pintype "passive"))
      (node (ref "J6") (pin "6") (pinfunction "6_6") (pintype "passive"))
      (node (ref "J7") (pin "1") (pinfunction "GND_1") (pintype "passive"))
      (node (ref "J7") (pin "14") (pinfunction "GND_14") (pintype "passive"))
      (node (ref "J8") (pin "4") (pinfunction "4_4") (pintype "passive"))
      (node (ref "J9") (pin "3") (pinfunction "3_3") (pintype "passive"))
      (node (ref "LB") (pin "4") (pinfunction "4_4") (pintype "passive"))
      (node (ref "LF") (pin "4") (pinfunction "4_4") (pintype "passive"))
      (node (ref "Q31") (pin "3") (pinfunction "S_3") (pintype "passive"))
      (node (ref "Q32") (pin "3") (pinfunction "S_3") (pintype "passive"))
      (node (ref "Q34") (pin "3") (pinfunction "S_3") (pintype "passive"))
      (node (ref "Q35") (pin "3") (pinfunction "S_3") (pintype "passive"))
      (node (ref "R62") (pin "2") (pinfunction "2_2") (pintype "passive"))
      (node (ref "R65") (pin "2") (pinfunction "2_2") (pintype "passive"))
      (node (ref "R81") (pin "1") (pinfunction "1_1") (pintype "passive"))
      (node (ref "R83") (pin "1") (pinfunction "1_1") (pintype "passive"))
      (node (ref "RB") (pin "4") (pinfunction "4_4") (pintype "passive"))
      (node (ref "RF") (pin "4") (pinfunction "4_4") (pintype "passive"))
    )
    (net (code "70") (name "Net-(Q28-Gate)") (class "Default")
      (node (ref "Q28") (pin "1") (pinfunction "Gate_1") (pintype "passive"))
      (node (ref "Q31") (pin "2") (pinfunction "D_2") (pintype "passive"))
      (node (ref "R86") (pin "2") (pinfunction "2_2") (pintype "passive"))
      (node (ref "R88") (pin "1") (pinfunction "1_1") (pintype "passive"))
    )
    (net (code "71") (name "Net-(Q29-Gate)") (class "Default")
      (node (ref "Q29") (pin "1") (pinfunction "Gate_1") (pintype "passive"))
      (node (ref "Q32") (pin "2") (pinfunction "D_2") (pintype "passive"))
      (node (ref "R87") (pin "2") (pinfunction "2_2") (pintype "passive"))
      (node (ref "R89") (pin "1") (pinfunction "1_1") (pintype "passive"))
    )
    (net (code "72") (name "Net-(Q30-Gate)") (class "Default")
      (node (ref "Q30") (pin "1") (pinfunction "Gate_1") (pintype "passive"))
      (node (ref "Q34") (pin "2") (pinfunction "D_2") (pintype "passive"))
      (node (ref "R90") (pin "2") (pinfunction "2_2") (pintype "passive"))
      (node (ref "R92") (pin "1") (pinfunction "1_1") (pintype "passive"))
    )
    (net (code "73") (name "Net-(Q33-Gate)") (class "Default")
      (node (ref "Q33") (pin "1") (pinfunction "Gate_1") (pintype "passive"))
      (node (ref "Q35") (pin "2") (pinfunction "D_2") (pintype "passive"))
      (node (ref "R91") (pin "2") (pinfunction "2_2") (pintype "passive"))
      (node (ref "R93") (pin "1") (pinfunction "1_1") (pintype "passive"))
    )
    (net (code "74") (name "unconnected-(Current_Battery-Pad6)") (class "Default")
      (node (ref "Current_Battery") (pin "6") (pinfunction "6_6") (pintype "passive+no_connect"))
    )
    (net (code "75") (name "unconnected-(Current_Motor-Pad6)") (class "Default")
      (node (ref "Current_Motor") (pin "6") (pinfunction "6_6") (pintype "passive+no_connect"))
    )
    (net (code "76") (name "unconnected-(IMU-3V3-Pad8)") (class "Default")
      (node (ref "IMU") (pin "8") (pinfunction "3V3_8") (pintype "passive+no_connect"))
    )
    (net (code "77") (name "unconnected-(IMU-GND-Pad7)") (class "Default")
      (node (ref "IMU") (pin "7") (pinfunction "GND_7") (pintype "passive+no_connect"))
    )
    (net (code "78") (name "unconnected-(IMU-INT-Pad6)") (class "Default")
      (node (ref "IMU") (pin "6") (pinfunction "INT_6") (pintype "passive+no_connect"))
    )
    (net (code "79") (name "unconnected-(IMU-SAFE-Pad5)") (class "Default")
      (node (ref "IMU") (pin "5") (pinfunction "SAFE_5") (pintype "passive+no_connect"))
    )
    (net (code "80") (name "unconnected-(IMU-SCL-Pad10)") (class "Default")
      (node (ref "IMU") (pin "10") (pinfunction "SCL_10") (pintype "passive+no_connect"))
    )
    (net (code "81") (name "unconnected-(IMU-SDA-Pad9)") (class "Default")
      (node (ref "IMU") (pin "9") (pinfunction "SDA_9") (pintype "passive+no_connect"))
    )
    (net (code "82") (name "unconnected-(J7-3V3-Pad3)") (class "Default")
      (node (ref "J7") (pin "3") (pinfunction "3V3_3") (pintype "passive+no_connect"))
    )
    (net (code "83") (name "unconnected-(J7-3V3-Pad15)") (class "Default")
      (node (ref "J7") (pin "15") (pinfunction "3V3_15") (pintype "passive+no_connect"))
    )
    (net (code "84") (name "unconnected-(J7-FENCE-Pad8)") (class "Default")
      (node (ref "J7") (pin "8") (pinfunction "FENCE_8") (pintype "passive+no_connect"))
    )
    (net (code "85") (name "unconnected-(J7-INT-Pad13)") (class "Default")
      (node (ref "J7") (pin "13") (pinfunction "INT_13") (pintype "passive+no_connect"))
    )
    (net (code "86") (name "unconnected-(J7-PPS-Pad10)") (class "Default")
      (node (ref "J7") (pin "10") (pinfunction "PPS_10") (pintype "passive+no_connect"))
    )
    (net (code "87") (name "unconnected-(J7-RTK-Pad9)") (class "Default")
      (node (ref "J7") (pin "9") (pinfunction "RTK_9") (pintype "passive+no_connect"))
    )
    (net (code "88") (name "unconnected-(J7-SCK-Pad7)") (class "Default")
      (node (ref "J7") (pin "7") (pinfunction "SCK_7") (pintype "passive+no_connect"))
    )
    (net (code "89") (name "unconnected-(J7-{slash}CS-Pad4)") (class "Default")
      (node (ref "J7") (pin "4") (pinfunction "/CS_4") (pintype "passive+no_connect"))
    )
    (net (code "90") (name "unconnected-(J7-{slash}RST-Pad11)") (class "Default")
      (node (ref "J7") (pin "11") (pinfunction "/RST_11") (pintype "passive+no_connect"))
    )
    (net (code "91") (name "unconnected-(J7-{slash}SAFE-Pad12)") (class "Default")
      (node (ref "J7") (pin "12") (pinfunction "/SAFE_12") (pintype "passive+no_connect"))
    )
  )
)
